# midi_pad_laser_test.net
KiCad netlist of a schematic drawn in EAGLE
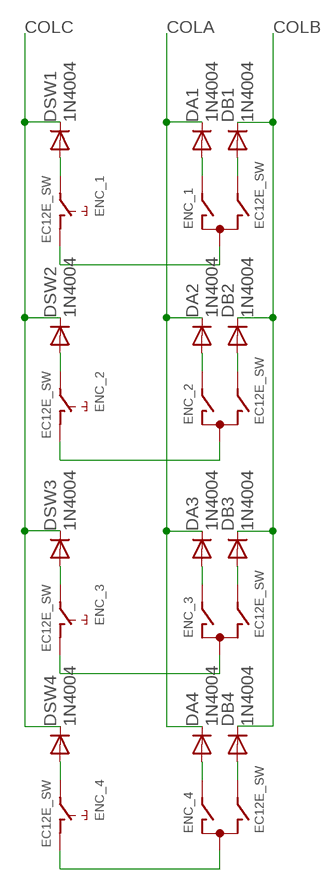
[diagram p0: schematic, sheet 1]

(export (version "E")
  (design (tool "Eeschema 10.0.6"))
  (components
    (comp (ref "DA1")
      (value "1N4004")
      (footprint "eagle-import:DO41-10")
      (libsource (lib "eagle-import") (part "1N4004"))
    )
    (comp (ref "DA2")
      (value "1N4004")
      (footprint "eagle-import:DO41-10")
      (libsource (lib "eagle-import") (part "1N4004"))
    )
    (comp (ref "DA3")
      (value "1N4004")
      (footprint "eagle-import:DO41-10")
      (libsource (lib "eagle-import") (part "1N4004"))
    )
    (comp (ref "DA4")
      (value "1N4004")
      (footprint "eagle-import:DO41-10")
      (libsource (lib "eagle-import") (part "1N4004"))
    )
    (comp (ref "DB1")
      (value "1N4004")
      (footprint "eagle-import:DO41-10")
      (libsource (lib "eagle-import") (part "1N4004"))
    )
    (comp (ref "DB2")
      (value "1N4004")
      (footprint "eagle-import:DO41-10")
      (libsource (lib "eagle-import") (part "1N4004"))
    )
    (comp (ref "DB3")
      (value "1N4004")
      (footprint "eagle-import:DO41-10")
      (libsource (lib "eagle-import") (part "1N4004"))
    )
    (comp (ref "DB4")
      (value "1N4004")
      (footprint "eagle-import:DO41-10")
      (libsource (lib "eagle-import") (part "1N4004"))
    )
    (comp (ref "DSW1")
      (value "1N4004")
      (footprint "eagle-import:DO41-10")
      (libsource (lib "eagle-import") (part "1N4004"))
    )
    (comp (ref "DSW2")
      (value "1N4004")
      (footprint "eagle-import:DO41-10")
      (libsource (lib "eagle-import") (part "1N4004"))
    )
    (comp (ref "DSW3")
      (value "1N4004")
      (footprint "eagle-import:DO41-10")
      (libsource (lib "eagle-import") (part "1N4004"))
    )
    (comp (ref "DSW4")
      (value "1N4004")
      (footprint "eagle-import:DO41-10")
      (libsource (lib "eagle-import") (part "1N4004"))
    )
    (comp (ref "ENC_1")
      (value "EC12E_SW")
      (footprint "eagle-import:ALPS_EC12E_SW")
      (fields (field (name "MPN") "EC12E2424407"))
      (libsource (lib "eagle-import") (part "EC12E_SW"))
    )
    (comp (ref "ENC_2")
      (value "EC12E_SW")
      (footprint "eagle-import:ALPS_EC12E_SW")
      (fields (field (name "MPN") "EC12E2424407"))
      (libsource (lib "eagle-import") (part "EC12E_SW"))
    )
    (comp (ref "ENC_3")
      (value "EC12E_SW")
      (footprint "eagle-import:ALPS_EC12E_SW")
      (fields (field (name "MPN") "EC12E2424407"))
      (libsource (lib "eagle-import") (part "EC12E_SW"))
    )
    (comp (ref "ENC_4")
      (value "EC12E_SW")
      (footprint "eagle-import:ALPS_EC12E_SW")
      (fields (field (name "MPN") "EC12E2424407"))
      (libsource (lib "eagle-import") (part "EC12E_SW"))
    )
  )
  (nets
    (net (code "1") (name "/COLA") (class "Default")
      (node (ref "DA1") (pin "C") (pinfunction "C_C") (pintype "passive"))
      (node (ref "DA2") (pin "C") (pinfunction "C_C") (pintype "passive"))
      (node (ref "DA3") (pin "C") (pinfunction "C_C") (pintype "passive"))
      (node (ref "DA4") (pin "C") (pinfunction "C_C") (pintype "passive"))
    )
    (net (code "2") (name "/COLB") (class "Default")
      (node (ref "DB1") (pin "C") (pinfunction "C_C") (pintype "passive"))
      (node (ref "DB2") (pin "C") (pinfunction "C_C") (pintype "passive"))
      (node (ref "DB3") (pin "C") (pinfunction "C_C") (pintype "passive"))
      (node (ref "DB4") (pin "C") (pinfunction "C_C") (pintype "passive"))
    )
    (net (code "3") (name "/COLC") (class "Default")
      (node (ref "DSW1") (pin "C") (pinfunction "C_C") (pintype "passive"))
      (node (ref "DSW2") (pin "C") (pinfunction "C_C") (pintype "passive"))
      (node (ref "DSW3") (pin "C") (pinfunction "C_C") (pintype "passive"))
      (node (ref "DSW4") (pin "C") (pinfunction "C_C") (pintype "passive"))
    )
    (net (code "4") (name "Net-(DA1-PadA)") (class "Default")
      (node (ref "DA1") (pin "A") (pinfunction "A_A") (pintype "passive"))
      (node (ref "ENC_1") (pin "A") (pinfunction "A_A") (pintype "passive"))
    )
    (net (code "5") (name "Net-(DA2-PadA)") (class "Default")
      (node (ref "DA2") (pin "A") (pinfunction "A_A") (pintype "passive"))
      (node (ref "ENC_2") (pin "A") (pinfunction "A_A") (pintype "passive"))
    )
    (net (code "6") (name "Net-(DA3-PadA)") (class "Default")
      (node (ref "DA3") (pin "A") (pinfunction "A_A") (pintype "passive"))
      (node (ref "ENC_3") (pin "A") (pinfunction "A_A") (pintype "passive"))
    )
    (net (code "7") (name "Net-(DA4-PadA)") (class "Default")
      (node (ref "DA4") (pin "A") (pinfunction "A_A") (pintype "passive"))
      (node (ref "ENC_4") (pin "A") (pinfunction "A_A") (pintype "passive"))
    )
    (net (code "8") (name "Net-(DB1-PadA)") (class "Default")
      (node (ref "DB1") (pin "A") (pinfunction "A_A") (pintype "passive"))
      (node (ref "ENC_1") (pin "B") (pinfunction "B_B") (pintype "passive"))
    )
    (net (code "9") (name "Net-(DB2-PadA)") (class "Default")
      (node (ref "DB2") (pin "A") (pinfunction "A_A") (pintype "passive"))
      (node (ref "ENC_2") (pin "B") (pinfunction "B_B") (pintype "passive"))
    )
    (net (code "10") (name "Net-(DB3-PadA)") (class "Default")
      (node (ref "DB3") (pin "A") (pinfunction "A_A") (pintype "passive"))
      (node (ref "ENC_3") (pin "B") (pinfunction "B_B") (pintype "passive"))
    )
    (net (code "11") (name "Net-(DB4-PadA)") (class "Default")
      (node (ref "DB4") (pin "A") (pinfunction "A_A") (pintype "passive"))
      (node (ref "ENC_4") (pin "B") (pinfunction "B_B") (pintype "passive"))
    )
    (net (code "12") (name "Net-(ENC_1B-1)") (class "Default")
      (node (ref "ENC_1") (pin "C") (pinfunction "C_C") (pintype "passive"))
      (node (ref "ENC_1") (pin "D") (pinfunction "1_D") (pintype "passive"))
    )
    (net (code "13") (name "Net-(ENC_1B-2)") (class "Default")
      (node (ref "DSW1") (pin "A") (pinfunction "A_A") (pintype "passive"))
      (node (ref "ENC_1") (pin "E") (pinfunction "2_E") (pintype "passive"))
    )
    (net (code "14") (name "Net-(ENC_2B-1)") (class "Default")
      (node (ref "ENC_2") (pin "C") (pinfunction "C_C") (pintype "passive"))
      (node (ref "ENC_2") (pin "D") (pinfunction "1_D") (pintype "passive"))
    )
    (net (code "15") (name "Net-(ENC_2B-2)") (class "Default")
      (node (ref "DSW2") (pin "A") (pinfunction "A_A") (pintype "passive"))
      (node (ref "ENC_2") (pin "E") (pinfunction "2_E") (pintype "passive"))
    )
    (net (code "16") (name "Net-(ENC_3B-1)") (class "Default")
      (node (ref "ENC_3") (pin "C") (pinfunction "C_C") (pintype "passive"))
      (node (ref "ENC_3") (pin "D") (pinfunction "1_D") (pintype "passive"))
    )
    (net (code "17") (name "Net-(ENC_3B-2)") (class "Default")
      (node (ref "DSW3") (pin "A") (pinfunction "A_A") (pintype "passive"))
      (node (ref "ENC_3") (pin "E") (pinfunction "2_E") (pintype "passive"))
    )
    (net (code "18") (name "Net-(ENC_4B-1)") (class "Default")
      (node (ref "ENC_4") (pin "C") (pinfunction "C_C") (pintype "passive"))
      (node (ref "ENC_4") (pin "D") (pinfunction "1_D") (pintype "passive"))
    )
    (net (code "19") (name "Net-(ENC_4B-2)") (class "Default")
      (node (ref "DSW4") (pin "A") (pinfunction "A_A") (pintype "passive"))
      (node (ref "ENC_4") (pin "E") (pinfunction "2_E") (pintype "passive"))
    )
  )
)
